# Main.net
KiCad netlist of a schematic drawn in Altium Designer
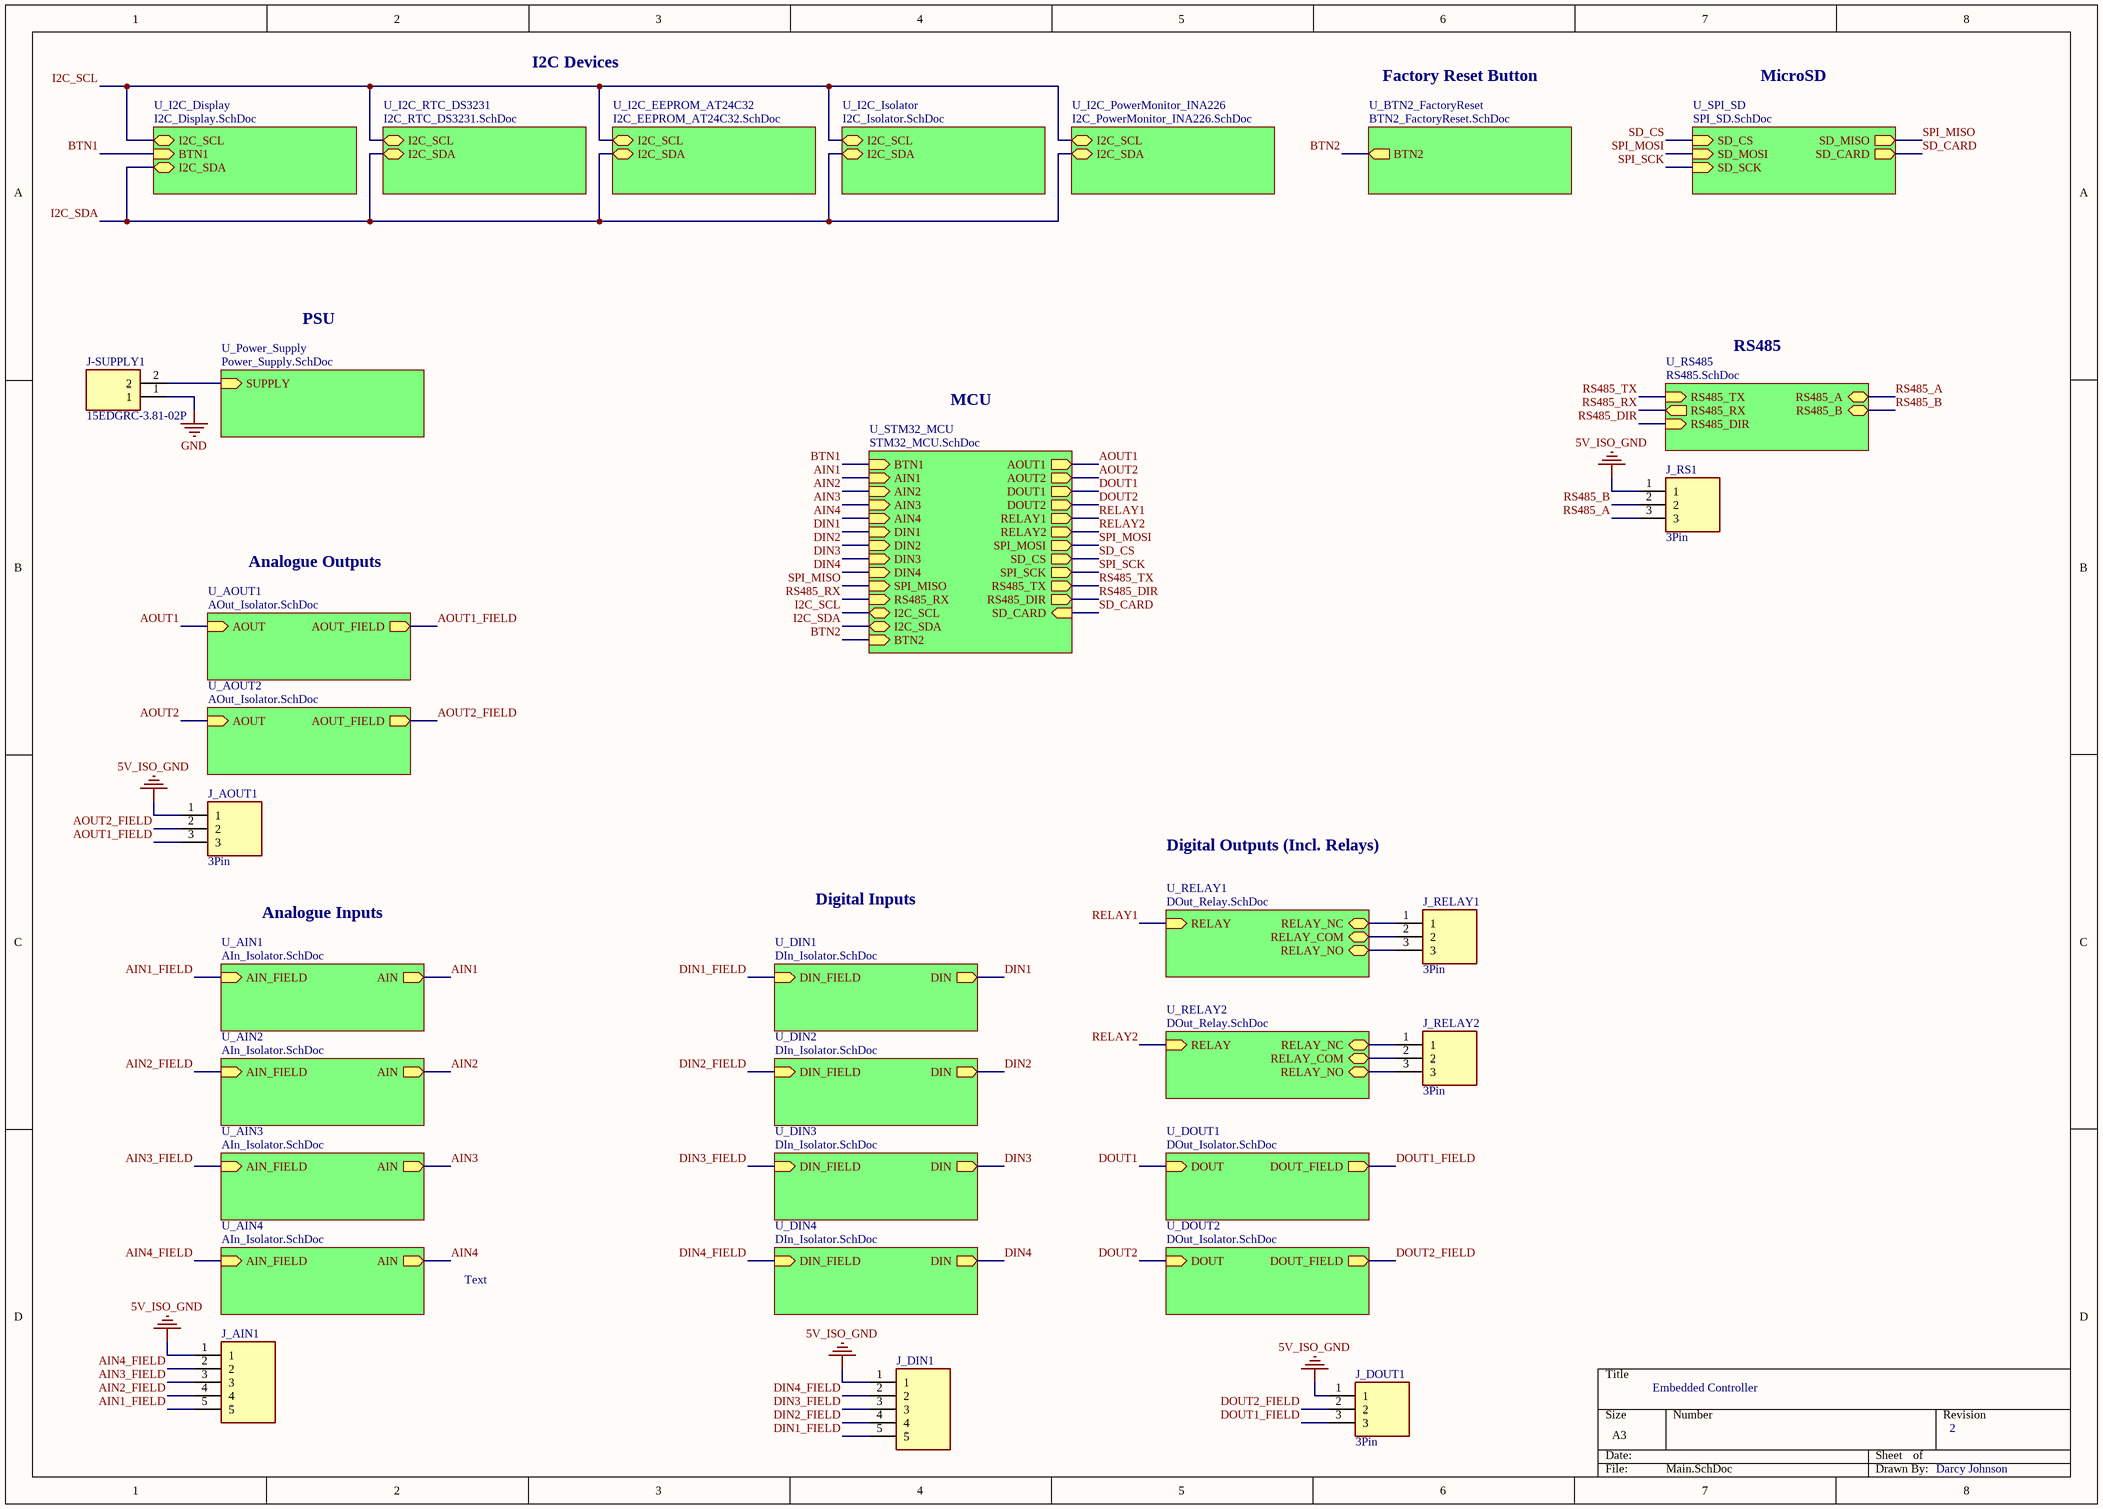
[diagram p0: Main.SchDoc]

(export (version "E")
  (design (tool "Eeschema 10.0.6"))
  (components
    (comp (ref "J-SUPPLY1")
      (value "15EDGRC-3.81-02P")
      (footprint "15EDGRC-3.81-02P")
      (fields (field (name "MANUFACTURER_PART_NUMBER") "15EDGRC-3.81-02P-14-00A(H)"))
      (libsource (lib "15EDGRC-3.81-02P") (part "15EDGRC-3.81-02P"))
    )
    (comp (ref "J_AIN1")
      (value "~")
      (footprint "15EDGRC-3.81-05P:15EDGRC-3.81-05P")
      (fields (field (name "MANUFACTURER_PART_NUMBER") "15EDGRC-3.81-02P-14-00A(H)"))
      (libsource (lib "15EDGRC-3.81") (part "15EDGRC-3.81-05P"))
    )
    (comp (ref "J_AOUT1")
      (value "3Pin")
      (footprint "15EDGRC-3.81-03P")
      (fields (field (name "MANUFACTURER_PART_NUMBER") "15EDGRC-3.81-02P-14-00A(H)"))
      (libsource (lib "15EDGRC-3.81-03P") (part "15EDGRC-3.81-03P"))
    )
    (comp (ref "J_DIN1")
      (value "~")
      (footprint "15EDGRC-3.81-05P:15EDGRC-3.81-05P")
      (fields (field (name "MANUFACTURER_PART_NUMBER") "15EDGRC-3.81-02P-14-00A(H)"))
      (libsource (lib "15EDGRC-3.81") (part "15EDGRC-3.81-05P"))
    )
    (comp (ref "J_DOUT1")
      (value "3Pin")
      (footprint "15EDGRC-3.81-03P")
      (fields (field (name "MANUFACTURER_PART_NUMBER") "15EDGRC-3.81-02P-14-00A(H)"))
      (libsource (lib "15EDGRC-3.81-03P") (part "15EDGRC-3.81-03P"))
    )
    (comp (ref "J_RELAY1")
      (value "3Pin")
      (footprint "15EDGRC-3.81-03P")
      (fields (field (name "MANUFACTURER_PART_NUMBER") "15EDGRC-3.81-02P-14-00A(H)"))
      (libsource (lib "15EDGRC-3.81-03P") (part "15EDGRC-3.81-03P"))
    )
    (comp (ref "J_RELAY2")
      (value "3Pin")
      (footprint "15EDGRC-3.81-03P")
      (fields (field (name "MANUFACTURER_PART_NUMBER") "15EDGRC-3.81-02P-14-00A(H)"))
      (libsource (lib "15EDGRC-3.81-03P") (part "15EDGRC-3.81-03P"))
    )
    (comp (ref "J_RS1")
      (value "3Pin")
      (footprint "15EDGRC-3.81-03P")
      (fields (field (name "MANUFACTURER_PART_NUMBER") "15EDGRC-3.81-02P-14-00A(H)"))
      (libsource (lib "15EDGRC-3.81-03P") (part "15EDGRC-3.81-03P"))
    )
  )
  (nets
    (net (code "2") (name "/AIN1_FIELD") (class "Default")
      (node (ref "J_AIN1") (pin "5") (pinfunction "5_5") (pintype "passive"))
    )
    (net (code "4") (name "/AIN2_FIELD") (class "Default")
      (node (ref "J_AIN1") (pin "4") (pinfunction "4_4") (pintype "passive"))
    )
    (net (code "6") (name "/AIN3_FIELD") (class "Default")
      (node (ref "J_AIN1") (pin "3") (pinfunction "3_3") (pintype "passive"))
    )
    (net (code "8") (name "/AIN4_FIELD") (class "Default")
      (node (ref "J_AIN1") (pin "2") (pinfunction "2_2") (pintype "passive"))
    )
    (net (code "10") (name "/AOUT1_FIELD") (class "Default")
      (node (ref "J_AOUT1") (pin "3") (pinfunction "3_3") (pintype "passive"))
    )
    (net (code "12") (name "/AOUT2_FIELD") (class "Default")
      (node (ref "J_AOUT1") (pin "2") (pinfunction "2_2") (pintype "passive"))
    )
    (net (code "16") (name "/DIN1_FIELD") (class "Default")
      (node (ref "J_DIN1") (pin "5") (pinfunction "5_5") (pintype "passive"))
    )
    (net (code "18") (name "/DIN2_FIELD") (class "Default")
      (node (ref "J_DIN1") (pin "4") (pinfunction "4_4") (pintype "passive"))
    )
    (net (code "20") (name "/DIN3_FIELD") (class "Default")
      (node (ref "J_DIN1") (pin "3") (pinfunction "3_3") (pintype "passive"))
    )
    (net (code "22") (name "/DIN4_FIELD") (class "Default")
      (node (ref "J_DIN1") (pin "2") (pinfunction "2_2") (pintype "passive"))
    )
    (net (code "24") (name "/DOUT1_FIELD") (class "Default")
      (node (ref "J_DOUT1") (pin "3") (pinfunction "3_3") (pintype "passive"))
    )
    (net (code "26") (name "/DOUT2_FIELD") (class "Default")
      (node (ref "J_DOUT1") (pin "2") (pinfunction "2_2") (pintype "passive"))
    )
    (net (code "31") (name "/RELAY_COM") (class "Default")
      (node (ref "J_RELAY1") (pin "2") (pinfunction "2_2") (pintype "passive"))
    )
    (net (code "32") (name "/RELAY_COM_1") (class "Default")
      (node (ref "J_RELAY2") (pin "2") (pinfunction "2_2") (pintype "passive"))
    )
    (net (code "33") (name "/RELAY_NC") (class "Default")
      (node (ref "J_RELAY1") (pin "1") (pinfunction "1_1") (pintype "passive"))
    )
    (net (code "34") (name "/RELAY_NC_1") (class "Default")
      (node (ref "J_RELAY2") (pin "1") (pinfunction "1_1") (pintype "passive"))
    )
    (net (code "35") (name "/RELAY_NO") (class "Default")
      (node (ref "J_RELAY1") (pin "3") (pinfunction "3_3") (pintype "passive"))
    )
    (net (code "36") (name "/RELAY_NO_1") (class "Default")
      (node (ref "J_RELAY2") (pin "3") (pinfunction "3_3") (pintype "passive"))
    )
    (net (code "37") (name "/RS485_A") (class "Default")
      (node (ref "J_RS1") (pin "3") (pinfunction "3_3") (pintype "passive"))
    )
    (net (code "38") (name "/RS485_B") (class "Default")
      (node (ref "J_RS1") (pin "2") (pinfunction "2_2") (pintype "passive"))
    )
    (net (code "47") (name "/SUPPLY") (class "Default")
      (node (ref "J-SUPPLY1") (pin "2") (pinfunction "2_2") (pintype "passive"))
    )
    (net (code "48") (name "5V_ISO_GND") (class "Default")
      (node (ref "J_AIN1") (pin "1") (pinfunction "1_1") (pintype "passive"))
      (node (ref "J_AOUT1") (pin "1") (pinfunction "1_1") (pintype "passive"))
      (node (ref "J_DIN1") (pin "1") (pinfunction "1_1") (pintype "passive"))
      (node (ref "J_DOUT1") (pin "1") (pinfunction "1_1") (pintype "passive"))
      (node (ref "J_RS1") (pin "1") (pinfunction "1_1") (pintype "passive"))
    )
    (net (code "49") (name "GND") (class "Default")
      (node (ref "J-SUPPLY1") (pin "1") (pinfunction "1_1") (pintype "passive"))
    )
  )
)
